# Power1.net
KiCad netlist of a schematic drawn in Altium Designer
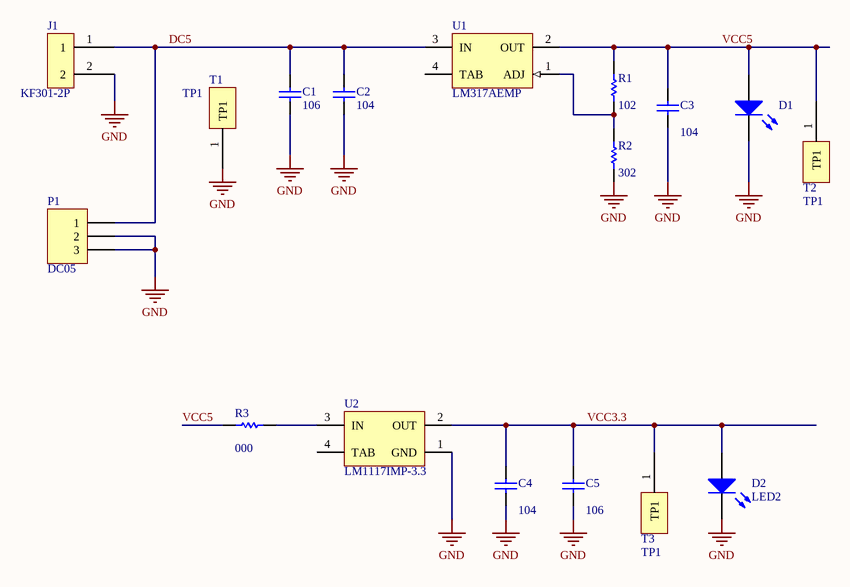
[diagram p0: Power1.SchDoc]

(export (version "E")
  (design (tool "Eeschema 10.0.6"))
  (components
    (comp (ref "C1")
      (value "106")
      (footprint "CAPC3216L")
      (description "Capacitor (Semiconductor SIM Model)")
      (fields (field (name "Comment") "Cap Semi") (field (name "PUBLISHER") "Altium Limited"))
      (libsource (lib "Miscellaneous Devices") (part "Cap Semi"))
    )
    (comp (ref "C2")
      (value "104")
      (footprint "CAPC3216L")
      (description "Capacitor (Semiconductor SIM Model)")
      (fields (field (name "Comment") "Cap Semi") (field (name "PUBLISHER") "Altium Limited"))
      (libsource (lib "Miscellaneous Devices") (part "Cap Semi"))
    )
    (comp (ref "C3")
      (value "104")
      (footprint "CAPC3216L")
      (description "Capacitor (Semiconductor SIM Model)")
      (fields (field (name "Comment") "Cap Semi") (field (name "PUBLISHER") "Altium Limited"))
      (libsource (lib "Miscellaneous Devices") (part "Cap Semi"))
    )
    (comp (ref "C4")
      (value "104")
      (footprint "CAPC3216L")
      (description "Capacitor (Semiconductor SIM Model)")
      (fields (field (name "Comment") "Cap Semi") (field (name "PUBLISHER") "Altium Limited"))
      (libsource (lib "Miscellaneous Devices") (part "Cap Semi"))
    )
    (comp (ref "C5")
      (value "106")
      (footprint "CAPC3216L")
      (description "Capacitor (Semiconductor SIM Model)")
      (fields (field (name "Comment") "Cap Semi") (field (name "PUBLISHER") "Altium Limited"))
      (libsource (lib "Miscellaneous Devices") (part "Cap Semi"))
    )
    (comp (ref "D1")
      (value "LED0")
      (footprint "CAPC2512L")
      (description "Typical INFRARED GaAs LED")
      (fields (field (name "PUBLISHER") "Altium Limited"))
      (libsource (lib "Miscellaneous Devices") (part "LED0"))
    )
    (comp (ref "D2")
      (value "LED2")
      (footprint "CAPC2512L")
      (description "Typical RED, GREEN, YELLOW, AMBER GaAs LED")
      (fields (field (name "PUBLISHER") "Altium Limited"))
      (libsource (lib "Miscellaneous Devices") (part "LED2"))
    )
    (comp (ref "J1") (value "KF301-2P") (footprint "KF301-2P") (libsource (lib "CHK-I") (part "KF301-2P")))
    (comp (ref "P1")
      (value "DC05")
      (footprint "DC005")
      (description "Header, 3-Pin")
      (fields (field (name "PUBLISHER") "Altium Limited"))
      (libsource (lib "Miscellaneous Connectors") (part "Header 3"))
    )
    (comp (ref "R1")
      (value "102")
      (footprint "RESC3216L")
      (description "Semiconductor Resistor")
      (fields (field (name "Comment") "Res Semi") (field (name "PUBLISHER") "Altium Limited"))
      (libsource (lib "Miscellaneous Devices") (part "Res Semi"))
    )
    (comp (ref "R2")
      (value "302")
      (footprint "RESC3216L")
      (description "Semiconductor Resistor")
      (fields (field (name "Comment") "Res Semi") (field (name "PUBLISHER") "Altium Limited"))
      (libsource (lib "Miscellaneous Devices") (part "Res Semi"))
    )
    (comp (ref "R3")
      (value "000")
      (footprint "RESC3216L")
      (description "Semiconductor Resistor")
      (fields (field (name "Comment") "Res Semi") (field (name "PUBLISHER") "Altium Limited"))
      (libsource (lib "Miscellaneous Devices") (part "Res Semi"))
    )
    (comp (ref "T1") (value "TP1") (footprint "TP1") (libsource (lib "") (part "TP1_1")))
    (comp (ref "T2") (value "TP1") (footprint "TP1") (libsource (lib "CHK-I") (part "TP1")))
    (comp (ref "T3") (value "TP1") (footprint "TP1") (libsource (lib "CHK-I") (part "TP1")))
    (comp (ref "U1")
      (value "LM317AEMP")
      (footprint "MP04A_L")
      (description "3-Terminal Adjustable Regulator")
      (fields
        (field (name "MANUFACTURER") "National Semiconductor")
        (field (name "DIGIKEYPARTNUMBER") "LM317AEMPCT-ND")
        (field (name "PUBLISHER") "Altium Limited")
      )
      (libsource (lib "NSC LDO") (part "LM317AEMP"))
    )
    (comp (ref "U2")
      (value "LM1117IMP-3.3")
      (footprint "MP04A_N")
      (description "800mA Low-Dropout Linear Regulator")
      (fields
        (field (name "MANUFACTURER") "National Semiconductor")
        (field (name "DIGIKEYPARTNUMBER") "LM1117IMP-3.3CT-ND")
        (field (name "PUBLISHER") "Altium Limited")
      )
      (libsource (lib "NSC LDO") (part "LM1117IMP-3.3"))
    )
  )
  (nets
    (net (code "1") (name "/DC5") (class "Default")
      (node (ref "C1") (pin "2") (pinfunction "2_2") (pintype "passive"))
      (node (ref "C2") (pin "2") (pinfunction "2_2") (pintype "passive"))
      (node (ref "J1") (pin "1") (pinfunction "1_1") (pintype "passive"))
      (node (ref "P1") (pin "1") (pinfunction "1_1") (pintype "passive"))
      (node (ref "U1") (pin "3") (pinfunction "IN_3") (pintype "power_in"))
    )
    (net (code "2") (name "/VCC3.3") (class "Default")
      (node (ref "C4") (pin "2") (pinfunction "2_2") (pintype "passive"))
      (node (ref "C5") (pin "2") (pinfunction "2_2") (pintype "passive"))
      (node (ref "D2") (pin "1") (pinfunction "A_1") (pintype "passive"))
      (node (ref "T3") (pin "1") (pinfunction "TP1_1") (pintype "passive"))
      (node (ref "U2") (pin "2") (pinfunction "OUT_2") (pintype "power_in"))
    )
    (net (code "3") (name "/VCC5") (class "Default")
      (node (ref "C3") (pin "2") (pinfunction "2_2") (pintype "passive"))
      (node (ref "D1") (pin "1") (pinfunction "A_1") (pintype "passive"))
      (node (ref "R1") (pin "2") (pinfunction "2_2") (pintype "passive"))
      (node (ref "R3") (pin "1") (pinfunction "1_1") (pintype "passive"))
      (node (ref "T2") (pin "1") (pinfunction "TP1_1") (pintype "passive"))
      (node (ref "U1") (pin "2") (pinfunction "OUT_2") (pintype "power_in"))
    )
    (net (code "4") (name "GND") (class "Default")
      (node (ref "C1") (pin "1") (pinfunction "1_1") (pintype "passive"))
      (node (ref "C2") (pin "1") (pinfunction "1_1") (pintype "passive"))
      (node (ref "C3") (pin "1") (pinfunction "1_1") (pintype "passive"))
      (node (ref "C4") (pin "1") (pinfunction "1_1") (pintype "passive"))
      (node (ref "C5") (pin "1") (pinfunction "1_1") (pintype "passive"))
      (node (ref "D1") (pin "2") (pinfunction "K_2") (pintype "passive"))
      (node (ref "D2") (pin "2") (pinfunction "K_2") (pintype "passive"))
      (node (ref "J1") (pin "2") (pinfunction "2_2") (pintype "passive"))
      (node (ref "P1") (pin "2") (pinfunction "2_2") (pintype "passive"))
      (node (ref "P1") (pin "3") (pinfunction "3_3") (pintype "passive"))
      (node (ref "R2") (pin "1") (pinfunction "1_1") (pintype "passive"))
      (node (ref "T1") (pin "1") (pinfunction "TP1_1") (pintype "passive"))
      (node (ref "U2") (pin "1") (pinfunction "GND_1") (pintype "power_in"))
    )
    (net (code "5") (name "Net-(U1-ADJ)") (class "Default")
      (node (ref "R1") (pin "1") (pinfunction "1_1") (pintype "passive"))
      (node (ref "R2") (pin "2") (pinfunction "2_2") (pintype "passive"))
      (node (ref "U1") (pin "1") (pinfunction "ADJ_1") (pintype "input"))
    )
    (net (code "6") (name "Net-(U2-IN)") (class "Default")
      (node (ref "R3") (pin "2") (pinfunction "2_2") (pintype "passive"))
      (node (ref "U2") (pin "3") (pinfunction "IN_3") (pintype "power_in"))
    )
    (net (code "7") (name "unconnected-(U1-TAB-Pad4)") (class "Default")
      (node (ref "U1") (pin "4") (pinfunction "TAB_4") (pintype "power_in"))
    )
    (net (code "8") (name "unconnected-(U2-TAB-Pad4)") (class "Default")
      (node (ref "U2") (pin "4") (pinfunction "TAB_4") (pintype "power_in"))
    )
  )
)
